# v2_board.net
KiCad netlist of a schematic drawn in EAGLE
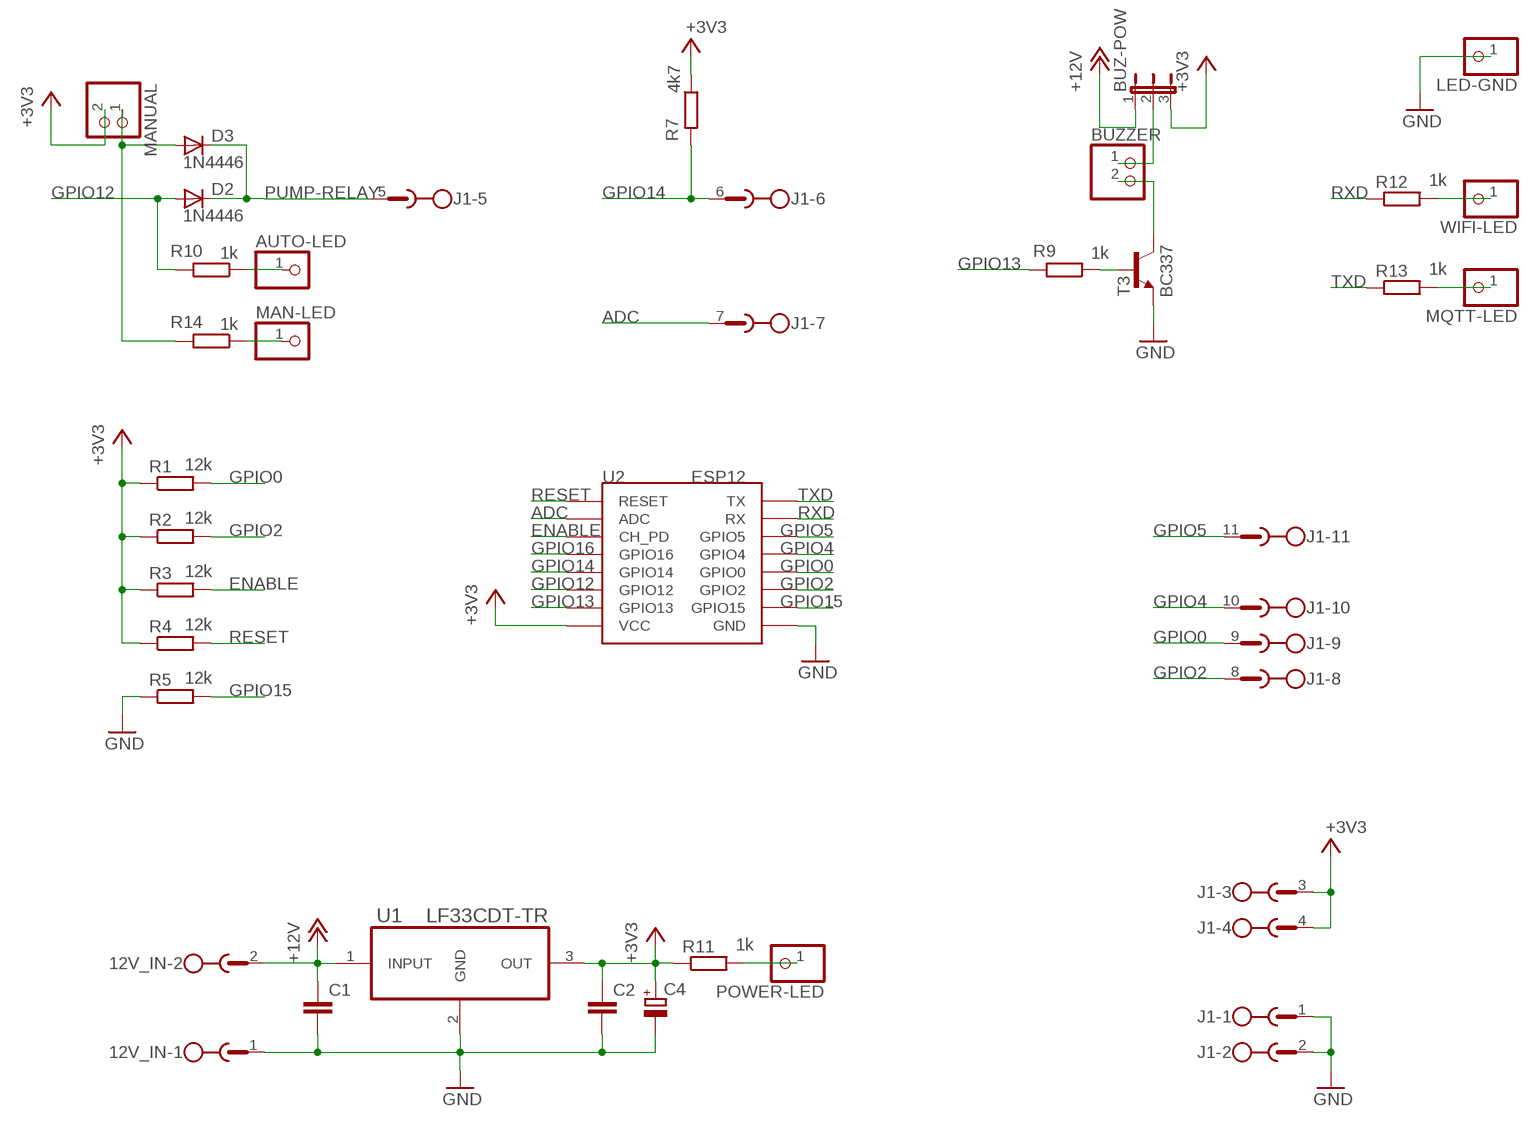
[diagram p0: schematic, sheet 1]

(export (version "E")
  (design (tool "Eeschema 10.0.6"))
  (components
    (comp (ref "12V_IN")
      (value "MSTBA2")
      (footprint "eagle-import:MSTBA2")
      (fields (field (name "MF") "FARNELL") (field (name "MPN") "1757242"))
      (libsource (lib "eagle-import") (part "MSTBA2"))
    )
    (comp (ref "AUTO-LED")
      (value "PINHD-1X1")
      (footprint "eagle-import:1X01")
      (libsource (lib "eagle-import") (part "PINHD-1X1"))
    )
    (comp (ref "BUZ-POW")
      (value "JP2E")
      (footprint "eagle-import:JP2")
      (libsource (lib "eagle-import") (part "JP2E"))
    )
    (comp (ref "BUZZER")
      (value "PINHD-1X2")
      (footprint "eagle-import:1X02")
      (libsource (lib "eagle-import") (part "PINHD-1X2"))
    )
    (comp (ref "C1")
      (value "C-EU025-025X050")
      (footprint "eagle-import:C025-025X050")
      (libsource (lib "eagle-import") (part "C-EU025-025X050"))
    )
    (comp (ref "C2")
      (value "C-EU025-025X050")
      (footprint "eagle-import:C025-025X050")
      (libsource (lib "eagle-import") (part "C-EU025-025X050"))
    )
    (comp (ref "C4")
      (value "CPOL-EUE3.5-8")
      (footprint "eagle-import:E3,5-8")
      (libsource (lib "eagle-import") (part "CPOL-EUE3.5-8"))
    )
    (comp (ref "D2")
      (value "1N4446")
      (footprint "eagle-import:DO35-10")
      (libsource (lib "eagle-import") (part "1N4446"))
    )
    (comp (ref "D3")
      (value "1N4446")
      (footprint "eagle-import:DO35-10")
      (libsource (lib "eagle-import") (part "1N4446"))
    )
    (comp (ref "J1")
      (value "MSTBA11")
      (footprint "eagle-import:MSTBA11")
      (libsource (lib "eagle-import") (part "MSTBA11"))
    )
    (comp (ref "LED-GND")
      (value "PINHD-1X1")
      (footprint "eagle-import:1X01")
      (libsource (lib "eagle-import") (part "PINHD-1X1"))
    )
    (comp (ref "MAN-LED")
      (value "PINHD-1X1")
      (footprint "eagle-import:1X01")
      (libsource (lib "eagle-import") (part "PINHD-1X1"))
    )
    (comp (ref "MANUAL")
      (value "PINHD-1X2")
      (footprint "eagle-import:1X02")
      (libsource (lib "eagle-import") (part "PINHD-1X2"))
    )
    (comp (ref "MQTT-LED")
      (value "PINHD-1X1")
      (footprint "eagle-import:1X01")
      (libsource (lib "eagle-import") (part "PINHD-1X1"))
    )
    (comp (ref "POWER-LED")
      (value "PINHD-1X1")
      (footprint "eagle-import:1X01")
      (libsource (lib "eagle-import") (part "PINHD-1X1"))
    )
    (comp (ref "R1")
      (value "12k")
      (footprint "eagle-import:R1206")
      (libsource (lib "eagle-import") (part "R-EU_R1206"))
    )
    (comp (ref "R2")
      (value "12k")
      (footprint "eagle-import:R1206")
      (libsource (lib "eagle-import") (part "R-EU_R1206"))
    )
    (comp (ref "R3")
      (value "12k")
      (footprint "eagle-import:R1206")
      (libsource (lib "eagle-import") (part "R-EU_R1206"))
    )
    (comp (ref "R4")
      (value "12k")
      (footprint "eagle-import:R1206")
      (libsource (lib "eagle-import") (part "R-EU_R1206"))
    )
    (comp (ref "R5")
      (value "12k")
      (footprint "eagle-import:R1206")
      (libsource (lib "eagle-import") (part "R-EU_R1206"))
    )
    (comp (ref "R7")
      (value "4k7")
      (footprint "eagle-import:R1206")
      (libsource (lib "eagle-import") (part "R-EU_R1206"))
    )
    (comp (ref "R9")
      (value "1k")
      (footprint "eagle-import:R1206")
      (libsource (lib "eagle-import") (part "R-EU_R1206"))
    )
    (comp (ref "R10")
      (value "1k")
      (footprint "eagle-import:R1206")
      (libsource (lib "eagle-import") (part "R-EU_R1206"))
    )
    (comp (ref "R11")
      (value "1k")
      (footprint "eagle-import:R1206")
      (libsource (lib "eagle-import") (part "R-EU_R1206"))
    )
    (comp (ref "R12")
      (value "1k")
      (footprint "eagle-import:R1206")
      (libsource (lib "eagle-import") (part "R-EU_R1206"))
    )
    (comp (ref "R13")
      (value "1k")
      (footprint "eagle-import:R1206")
      (libsource (lib "eagle-import") (part "R-EU_R1206"))
    )
    (comp (ref "R14")
      (value "1k")
      (footprint "eagle-import:R1206")
      (libsource (lib "eagle-import") (part "R-EU_R1206"))
    )
    (comp (ref "T3")
      (value "BC337")
      (footprint "eagle-import:TO92")
      (libsource (lib "eagle-import") (part "BC337"))
    )
    (comp (ref "U1")
      (value "LF33CDT-TR")
      (footprint "eagle-import:TO228P972X240-3N")
      (fields (field (name "MF") "STMicroelectronics"))
      (libsource (lib "eagle-import") (part "LF33CDT-TR"))
    )
    (comp (ref "U2")
      (value "ESP12")
      (footprint "eagle-import:ESP12")
      (fields (field (name "SPICEPREFIX") "X"))
      (libsource (lib "eagle-import") (part "ESP12"))
    )
    (comp (ref "WIFI-LED")
      (value "PINHD-1X1")
      (footprint "eagle-import:1X01")
      (libsource (lib "eagle-import") (part "PINHD-1X1"))
    )
  )
  (nets
    (net (code "1") (name "+3V3") (class "Default")
      (node (ref "BUZ-POW") (pin "3") (pinfunction "3_3") (pintype "passive"))
      (node (ref "C2") (pin "1") (pinfunction "1_1") (pintype "passive"))
      (node (ref "C4") (pin "+") (pinfunction "+_+") (pintype "passive"))
      (node (ref "J1") (pin "3") (pinfunction "1_3") (pintype "passive"))
      (node (ref "J1") (pin "4") (pinfunction "1_4") (pintype "passive"))
      (node (ref "MANUAL") (pin "2") (pinfunction "2_2") (pintype "passive"))
      (node (ref "R1") (pin "1") (pinfunction "1_1") (pintype "passive"))
      (node (ref "R11") (pin "1") (pinfunction "1_1") (pintype "passive"))
      (node (ref "R2") (pin "1") (pinfunction "1_1") (pintype "passive"))
      (node (ref "R3") (pin "1") (pinfunction "1_1") (pintype "passive"))
      (node (ref "R4") (pin "1") (pinfunction "1_1") (pintype "passive"))
      (node (ref "R7") (pin "1") (pinfunction "1_1") (pintype "passive"))
      (node (ref "U1") (pin "3") (pinfunction "OUT_3") (pintype "output"))
      (node (ref "U2") (pin "VCC") (pinfunction "VCC_VCC") (pintype "bidirectional"))
    )
    (net (code "2") (name "+12V") (class "Default")
      (node (ref "12V_IN") (pin "2") (pinfunction "1_2") (pintype "passive"))
      (node (ref "BUZ-POW") (pin "1") (pinfunction "1_1") (pintype "passive"))
      (node (ref "C1") (pin "1") (pinfunction "1_1") (pintype "passive"))
      (node (ref "U1") (pin "1") (pinfunction "INPUT_1") (pintype "input"))
    )
    (net (code "3") (name "/ADC") (class "Default")
      (node (ref "J1") (pin "7") (pinfunction "1_7") (pintype "passive"))
      (node (ref "U2") (pin "ADC") (pinfunction "ADC_ADC") (pintype "bidirectional"))
    )
    (net (code "4") (name "/ENABLE") (class "Default")
      (node (ref "R3") (pin "2") (pinfunction "2_2") (pintype "passive"))
      (node (ref "U2") (pin "CH_PD") (pinfunction "CH_PD_CH_PD") (pintype "bidirectional"))
    )
    (net (code "5") (name "/GPIO0") (class "Default")
      (node (ref "J1") (pin "9") (pinfunction "1_9") (pintype "passive"))
      (node (ref "R1") (pin "2") (pinfunction "2_2") (pintype "passive"))
      (node (ref "U2") (pin "GPIO0") (pinfunction "GPIO0_GPIO0") (pintype "bidirectional"))
    )
    (net (code "6") (name "/GPIO2") (class "Default")
      (node (ref "J1") (pin "8") (pinfunction "1_8") (pintype "passive"))
      (node (ref "R2") (pin "2") (pinfunction "2_2") (pintype "passive"))
      (node (ref "U2") (pin "GPIO2") (pinfunction "GPIO2_GPIO2") (pintype "bidirectional"))
    )
    (net (code "7") (name "/GPIO4") (class "Default")
      (node (ref "J1") (pin "10") (pinfunction "1_10") (pintype "passive"))
      (node (ref "U2") (pin "GPIO5") (pinfunction "GPIO4_GPIO5") (pintype "bidirectional"))
    )
    (net (code "8") (name "/GPIO5") (class "Default")
      (node (ref "J1") (pin "11") (pinfunction "1_11") (pintype "passive"))
      (node (ref "U2") (pin "GPIO4") (pinfunction "GPIO5_GPIO4") (pintype "bidirectional"))
    )
    (net (code "9") (name "/GPIO12") (class "Default")
      (node (ref "D2") (pin "A") (pinfunction "A_A") (pintype "passive"))
      (node (ref "R10") (pin "2") (pinfunction "2_2") (pintype "passive"))
      (node (ref "U2") (pin "GPIO12") (pinfunction "GPIO12_GPIO12") (pintype "bidirectional"))
    )
    (net (code "10") (name "/GPIO13") (class "Default")
      (node (ref "R9") (pin "2") (pinfunction "2_2") (pintype "passive"))
      (node (ref "U2") (pin "GPIO13") (pinfunction "GPIO13_GPIO13") (pintype "bidirectional"))
    )
    (net (code "11") (name "/GPIO14") (class "Default")
      (node (ref "J1") (pin "6") (pinfunction "1_6") (pintype "passive"))
      (node (ref "R7") (pin "2") (pinfunction "2_2") (pintype "passive"))
      (node (ref "U2") (pin "GPIO14") (pinfunction "GPIO14_GPIO14") (pintype "bidirectional"))
    )
    (net (code "12") (name "/GPIO15") (class "Default")
      (node (ref "R5") (pin "2") (pinfunction "2_2") (pintype "passive"))
      (node (ref "U2") (pin "GPIO15") (pinfunction "GPIO15_GPIO15") (pintype "bidirectional"))
    )
    (net (code "13") (name "/GPIO16") (class "Default")
      (node (ref "U2") (pin "GPIO16") (pinfunction "GPIO16_GPIO16") (pintype "bidirectional"))
    )
    (net (code "14") (name "/PUMP-RELAY") (class "Default")
      (node (ref "D2") (pin "C") (pinfunction "C_C") (pintype "passive"))
      (node (ref "D3") (pin "C") (pinfunction "C_C") (pintype "passive"))
      (node (ref "J1") (pin "5") (pinfunction "1_5") (pintype "passive"))
    )
    (net (code "15") (name "/RESET") (class "Default")
      (node (ref "R4") (pin "2") (pinfunction "2_2") (pintype "passive"))
      (node (ref "U2") (pin "RESET") (pinfunction "RESET_RESET") (pintype "bidirectional"))
    )
    (net (code "16") (name "/RXD") (class "Default")
      (node (ref "R12") (pin "1") (pinfunction "1_1") (pintype "passive"))
      (node (ref "U2") (pin "RX") (pinfunction "RX_RX") (pintype "bidirectional"))
    )
    (net (code "17") (name "/TXD") (class "Default")
      (node (ref "R13") (pin "1") (pinfunction "1_1") (pintype "passive"))
      (node (ref "U2") (pin "TX") (pinfunction "TX_TX") (pintype "bidirectional"))
    )
    (net (code "18") (name "GND") (class "Default")
      (node (ref "12V_IN") (pin "1") (pinfunction "1_1") (pintype "passive"))
      (node (ref "C1") (pin "2") (pinfunction "2_2") (pintype "passive"))
      (node (ref "C2") (pin "2") (pinfunction "2_2") (pintype "passive"))
      (node (ref "C4") (pin "-") (pinfunction "-_-") (pintype "passive"))
      (node (ref "J1") (pin "1") (pinfunction "1_1") (pintype "passive"))
      (node (ref "J1") (pin "2") (pinfunction "1_2") (pintype "passive"))
      (node (ref "LED-GND") (pin "1") (pinfunction "1_1") (pintype "passive"))
      (node (ref "R5") (pin "1") (pinfunction "1_1") (pintype "passive"))
      (node (ref "T3") (pin "1") (pinfunction "E_1") (pintype "passive"))
      (node (ref "U1") (pin "2") (pinfunction "GND_2") (pintype "passive"))
      (node (ref "U2") (pin "GND") (pinfunction "GND_GND") (pintype "bidirectional"))
    )
    (net (code "19") (name "Net-(AUTO-LED-Pad1)") (class "Default")
      (node (ref "AUTO-LED") (pin "1") (pinfunction "1_1") (pintype "passive"))
      (node (ref "R10") (pin "1") (pinfunction "1_1") (pintype "passive"))
    )
    (net (code "20") (name "Net-(BUZ-POW-Pad2)") (class "Default")
      (node (ref "BUZ-POW") (pin "2") (pinfunction "2_2") (pintype "passive"))
      (node (ref "BUZZER") (pin "1") (pinfunction "1_1") (pintype "passive"))
    )
    (net (code "21") (name "Net-(D3-PadA)") (class "Default")
      (node (ref "D3") (pin "A") (pinfunction "A_A") (pintype "passive"))
      (node (ref "MANUAL") (pin "1") (pinfunction "1_1") (pintype "passive"))
      (node (ref "R14") (pin "2") (pinfunction "2_2") (pintype "passive"))
    )
    (net (code "22") (name "Net-(MAN-LED-Pad1)") (class "Default")
      (node (ref "MAN-LED") (pin "1") (pinfunction "1_1") (pintype "passive"))
      (node (ref "R14") (pin "1") (pinfunction "1_1") (pintype "passive"))
    )
    (net (code "23") (name "Net-(MQTT-LED-Pad1)") (class "Default")
      (node (ref "MQTT-LED") (pin "1") (pinfunction "1_1") (pintype "passive"))
      (node (ref "R13") (pin "2") (pinfunction "2_2") (pintype "passive"))
    )
    (net (code "24") (name "Net-(POWER-LED-Pad1)") (class "Default")
      (node (ref "POWER-LED") (pin "1") (pinfunction "1_1") (pintype "passive"))
      (node (ref "R11") (pin "2") (pinfunction "2_2") (pintype "passive"))
    )
    (net (code "25") (name "Net-(R12-Pad2)") (class "Default")
      (node (ref "R12") (pin "2") (pinfunction "2_2") (pintype "passive"))
      (node (ref "WIFI-LED") (pin "1") (pinfunction "1_1") (pintype "passive"))
    )
    (net (code "26") (name "Net-(T3-B)") (class "Default")
      (node (ref "R9") (pin "1") (pinfunction "1_1") (pintype "passive"))
      (node (ref "T3") (pin "2") (pinfunction "B_2") (pintype "passive"))
    )
    (net (code "27") (name "Net-(T3-C)") (class "Default")
      (node (ref "BUZZER") (pin "2") (pinfunction "2_2") (pintype "passive"))
      (node (ref "T3") (pin "3") (pinfunction "C_3") (pintype "passive"))
    )
  )
)
